# SprinklerControllerRecover.net
KiCad netlist of a schematic drawn in EAGLE
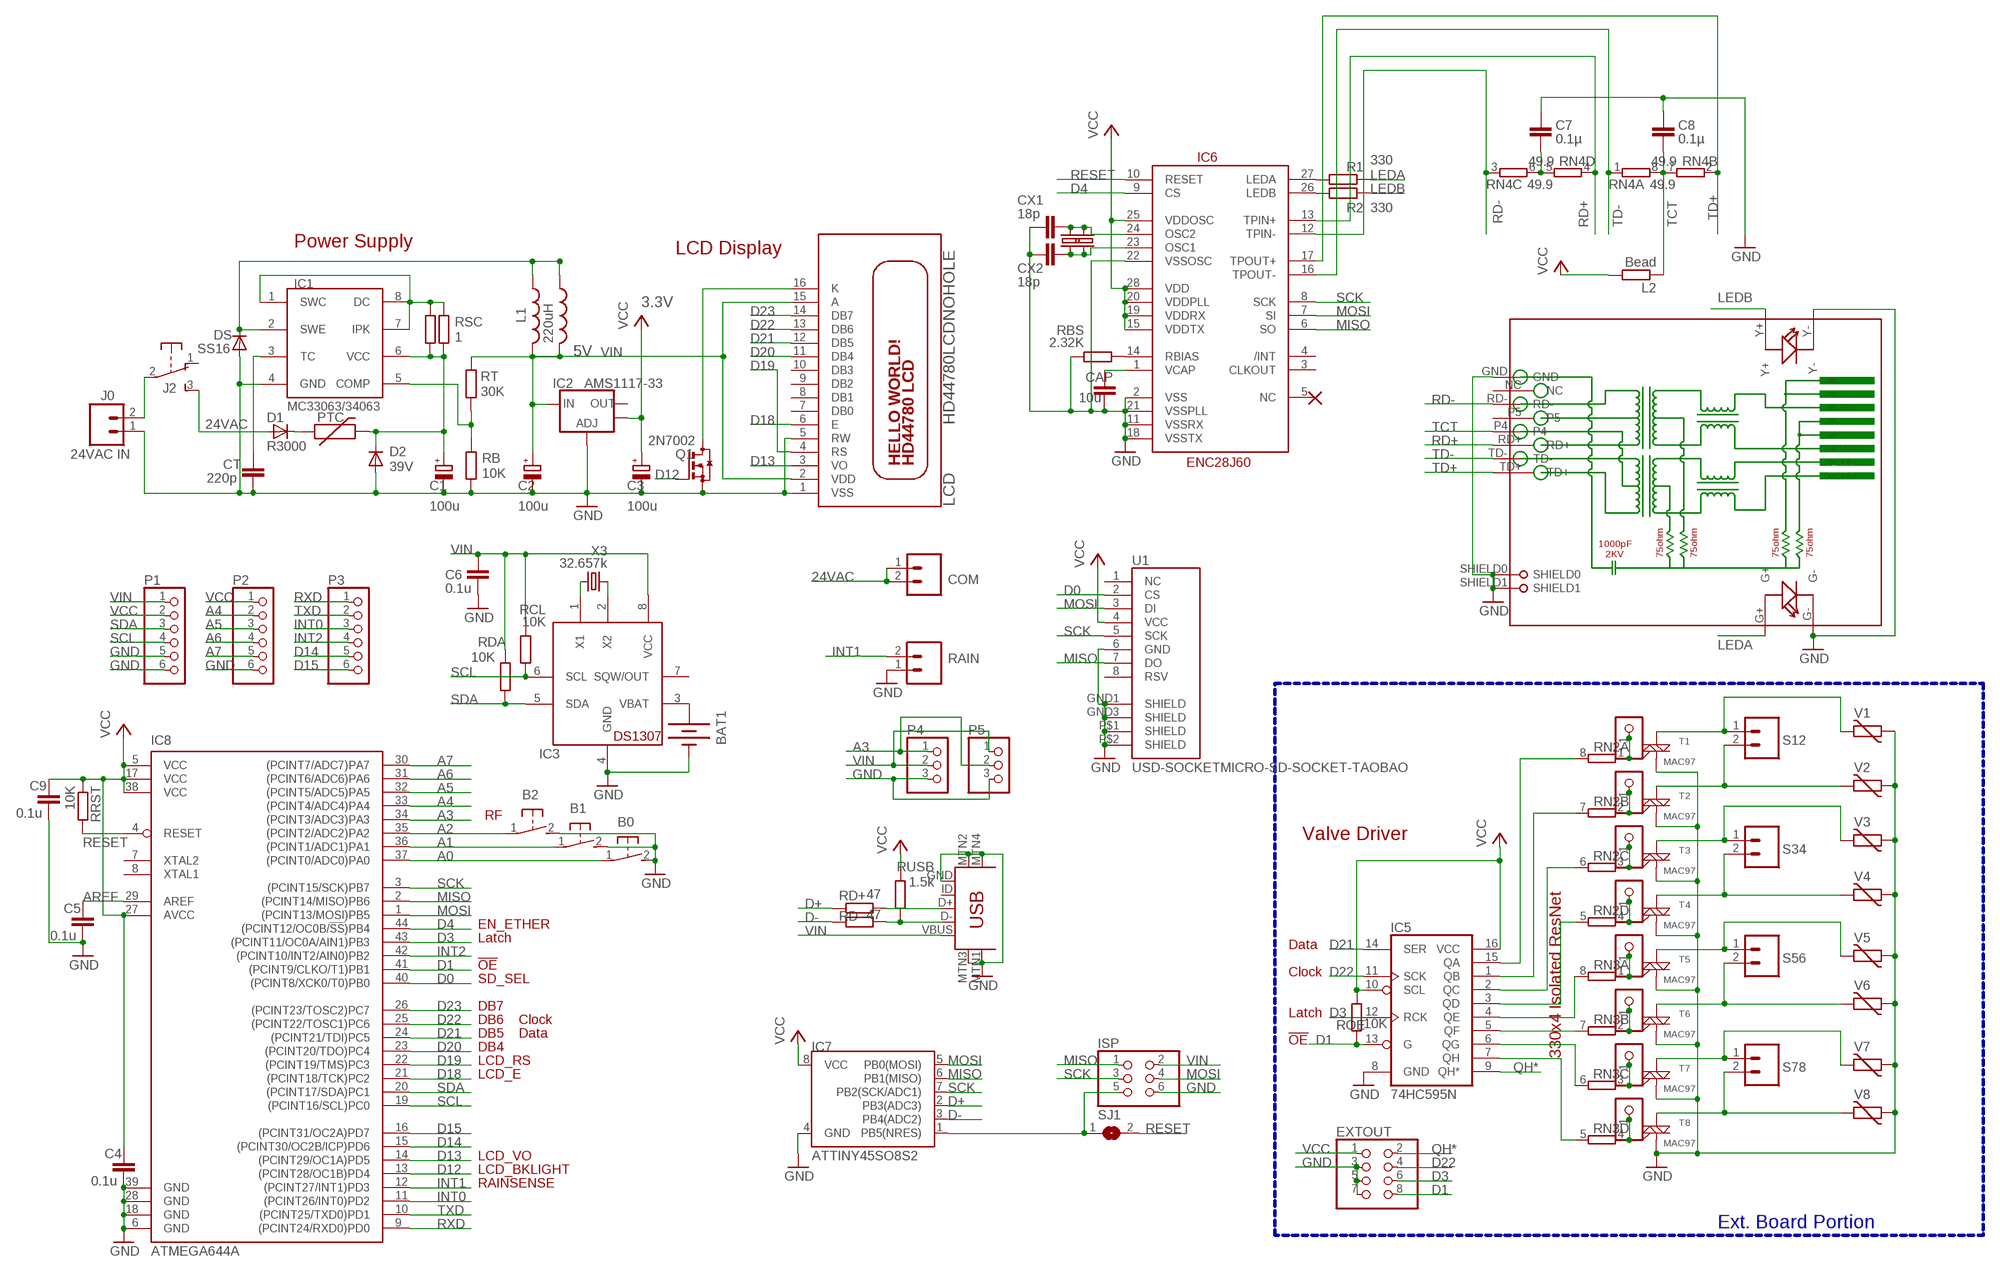
[diagram p0: schematic, sheet 1]

(export (version "E")
  (design (tool "Eeschema 10.0.6"))
  (components
    (comp (ref "B0")
      (value "31-XX")
      (footprint "eagle-import:B3F-31XX")
      (libsource (lib "eagle-import") (part "31-XX"))
    )
    (comp (ref "B1")
      (value "31-XX")
      (footprint "eagle-import:B3F-31XX")
      (libsource (lib "eagle-import") (part "31-XX"))
    )
    (comp (ref "B2")
      (value "31-XX")
      (footprint "eagle-import:B3F-31XX")
      (libsource (lib "eagle-import") (part "31-XX"))
    )
    (comp (ref "BAT1")
      (value "BATTERYBATTERY_12MM_SMT")
      (footprint "eagle-import:BATTCON_12MM_SMT")
      (libsource (lib "eagle-import") (part "BATTERYBATTERY_12MM_SMT"))
    )
    (comp (ref "C1")
      (value "100u")
      (footprint "eagle-import:E3,5-8")
      (libsource (lib "eagle-import") (part "CPOL-EUE3.5-8"))
    )
    (comp (ref "C2")
      (value "100u")
      (footprint "eagle-import:E2,5-5")
      (libsource (lib "eagle-import") (part "CPOL-EUE2.5-5"))
    )
    (comp (ref "C3")
      (value "100u")
      (footprint "eagle-import:E2,5-5")
      (libsource (lib "eagle-import") (part "CPOL-EUE2.5-5"))
    )
    (comp (ref "C4")
      (value "0.1u")
      (footprint "eagle-import:C0805")
      (libsource (lib "eagle-import") (part "C-EUC0805"))
    )
    (comp (ref "C5")
      (value "0.1u")
      (footprint "eagle-import:C0805")
      (libsource (lib "eagle-import") (part "C-EUC0805"))
    )
    (comp (ref "C6")
      (value "0.1u")
      (footprint "eagle-import:C0805")
      (libsource (lib "eagle-import") (part "C-EUC0805"))
    )
    (comp (ref "C7")
      (value "0.1µ")
      (footprint "eagle-import:C0805")
      (libsource (lib "eagle-import") (part "resistor_C-EUC0805"))
    )
    (comp (ref "C8")
      (value "0.1µ")
      (footprint "eagle-import:C0805")
      (libsource (lib "eagle-import") (part "resistor_C-EUC0805"))
    )
    (comp (ref "C9")
      (value "0.1u")
      (footprint "eagle-import:C0805")
      (libsource (lib "eagle-import") (part "C-EUC0805"))
    )
    (comp (ref "CAP")
      (value "10u")
      (footprint "eagle-import:C0805")
      (libsource (lib "eagle-import") (part "resistor_C-EUC0805"))
    )
    (comp (ref "COM")
      (value "M025MM")
      (footprint "eagle-import:SCREWTERMINAL-5MM-2")
      (libsource (lib "eagle-import") (part "M025MM"))
    )
    (comp (ref "CT")
      (value "220p")
      (footprint "eagle-import:C0805")
      (libsource (lib "eagle-import") (part "C-EUC0805"))
    )
    (comp (ref "CX1")
      (value "18p")
      (footprint "eagle-import:C0805")
      (libsource (lib "eagle-import") (part "resistor_C-EUC0805"))
    )
    (comp (ref "CX2")
      (value "18p")
      (footprint "eagle-import:C0805")
      (libsource (lib "eagle-import") (part "resistor_C-EUC0805"))
    )
    (comp (ref "D1")
      (value "R3000")
      (footprint "eagle-import:DO41-7.6")
      (libsource (lib "eagle-import") (part "DIODE-DO41-7.6"))
    )
    (comp (ref "D2")
      (value "39V")
      (footprint "eagle-import:DO41-7.6")
      (libsource (lib "eagle-import") (part "DIODE-DO41-7.6"))
    )
    (comp (ref "DS")
      (value "SS16")
      (footprint "eagle-import:DO214AC")
      (libsource (lib "eagle-import") (part "DIODE-DO214AC"))
    )
    (comp (ref "EXTOUT")
      (value "PINHD-2X4")
      (footprint "eagle-import:2X04")
      (libsource (lib "eagle-import") (part "PINHD-2X4"))
    )
    (comp (ref "IC1")
      (value "MC34063")
      (footprint "eagle-import:SO08")
      (libsource (lib "eagle-import") (part "MC33063/MC34063D"))
    )
    (comp (ref "IC2")
      (value "AMS1117-33")
      (footprint "eagle-import:SOT223")
      (libsource (lib "eagle-import") (part "V_REG_LM1117SOT223"))
    )
    (comp (ref "IC3")
      (value "DS1307")
      (footprint "eagle-import:SO08")
      (libsource (lib "eagle-import") (part "DS1307SOIC"))
    )
    (comp (ref "IC5")
      (value "74HC595N")
      (footprint "eagle-import:SO16")
      (libsource (lib "eagle-import") (part "74595DLS"))
    )
    (comp (ref "IC6")
      (value "ENC28J60")
      (footprint "eagle-import:SOIC28WLONG")
      (libsource (lib "eagle-import") (part "ENC28J60SO28LONG"))
    )
    (comp (ref "IC7")
      (value "ATTINY45SO8S2")
      (footprint "eagle-import:SO8S2")
      (libsource (lib "eagle-import") (part "ATTINY45SO8S2"))
    )
    (comp (ref "IC8")
      (value "ATMEGA644A")
      (footprint "eagle-import:TQFP44")
      (fields (field (name "MPN") "ATMEGA644PV-10AU"))
      (libsource (lib "eagle-import") (part "ATMEGA644A"))
    )
    (comp (ref "ISP")
      (value "PINHD-2X3")
      (footprint "eagle-import:2X03")
      (libsource (lib "eagle-import") (part "PINHD-2X3"))
    )
    (comp (ref "J0")
      (value "24VAC IN")
      (footprint "eagle-import:SCREWTERMINAL-5MM-2")
      (libsource (lib "eagle-import") (part "M025MM"))
    )
    (comp (ref "J2")
      (value "EG1206")
      (footprint "eagle-import:EG1206")
      (libsource (lib "eagle-import") (part "EG1206"))
    )
    (comp (ref "JP2")
      (value "PINHD-1X1CB")
      (footprint "eagle-import:1X01-CLEANBIG")
      (libsource (lib "eagle-import") (part "PINHD-1X1CB"))
    )
    (comp (ref "JP3")
      (value "PINHD-1X1CB")
      (footprint "eagle-import:1X01-CLEANBIG")
      (libsource (lib "eagle-import") (part "PINHD-1X1CB"))
    )
    (comp (ref "JP4")
      (value "PINHD-1X1CB")
      (footprint "eagle-import:1X01-CLEANBIG")
      (libsource (lib "eagle-import") (part "PINHD-1X1CB"))
    )
    (comp (ref "JP5")
      (value "PINHD-1X1CB")
      (footprint "eagle-import:1X01-CLEANBIG")
      (libsource (lib "eagle-import") (part "PINHD-1X1CB"))
    )
    (comp (ref "JP6")
      (value "PINHD-1X1CB")
      (footprint "eagle-import:1X01-CLEANBIG")
      (libsource (lib "eagle-import") (part "PINHD-1X1CB"))
    )
    (comp (ref "JP7")
      (value "PINHD-1X1CB")
      (footprint "eagle-import:1X01-CLEANBIG")
      (libsource (lib "eagle-import") (part "PINHD-1X1CB"))
    )
    (comp (ref "JP8")
      (value "PINHD-1X1CB")
      (footprint "eagle-import:1X01-CLEANBIG")
      (libsource (lib "eagle-import") (part "PINHD-1X1CB"))
    )
    (comp (ref "JP9")
      (value "PINHD-1X1CB")
      (footprint "eagle-import:1X01-CLEANBIG")
      (libsource (lib "eagle-import") (part "PINHD-1X1CB"))
    )
    (comp (ref "L1")
      (value "220uH")
      (footprint "eagle-import:6000-XXXX-RC")
      (libsource (lib "eagle-import") (part "L-US6000-XXX-RC"))
    )
    (comp (ref "L2")
      (value "Bead")
      (footprint "eagle-import:R0805")
      (libsource (lib "eagle-import") (part "R-EU_R0805"))
    )
    (comp (ref "L3")
      (value "220uH")
      (footprint "eagle-import:SRU1038")
      (libsource (lib "eagle-import") (part "INDUCTORSRU1038"))
    )
    (comp (ref "LCD")
      (value "HD44780LCDNOHOLE")
      (footprint "eagle-import:LCD1602A")
      (libsource (lib "eagle-import") (part "HD44780LCDNOHOLE"))
    )
    (comp (ref "P1")
      (value "PINHD-1X6CLEAN")
      (footprint "eagle-import:1X06-CLEAN")
      (libsource (lib "eagle-import") (part "PINHD-1X6CLEAN"))
    )
    (comp (ref "P2")
      (value "PINHD-1X6CLEAN")
      (footprint "eagle-import:1X06-CLEAN")
      (libsource (lib "eagle-import") (part "PINHD-1X6CLEAN"))
    )
    (comp (ref "P3")
      (value "PINHD-1X6CLEAN")
      (footprint "eagle-import:1X06-CLEAN")
      (libsource (lib "eagle-import") (part "PINHD-1X6CLEAN"))
    )
    (comp (ref "P4")
      (value "PINHD-1X3")
      (footprint "eagle-import:1X03")
      (libsource (lib "eagle-import") (part "PINHD-1X3"))
    )
    (comp (ref "P5")
      (value "PINHD-1X3")
      (footprint "eagle-import:1X03")
      (libsource (lib "eagle-import") (part "PINHD-1X3"))
    )
    (comp (ref "PTC")
      (value "PTC")
      (footprint "eagle-import:PTC")
      (libsource (lib "eagle-import") (part "PTCPTH"))
    )
    (comp (ref "Q1")
      (value "2N7002")
      (footprint "eagle-import:SOT23")
      (libsource (lib "eagle-import") (part "BSS123"))
    )
    (comp (ref "R1")
      (value "330")
      (footprint "eagle-import:R0805")
      (libsource (lib "eagle-import") (part "R-EU_R0805"))
    )
    (comp (ref "R2")
      (value "330")
      (footprint "eagle-import:R0805")
      (libsource (lib "eagle-import") (part "R-EU_R0805"))
    )
    (comp (ref "RAIN")
      (value "M025MM")
      (footprint "eagle-import:SCREWTERMINAL-5MM-2")
      (libsource (lib "eagle-import") (part "M025MM"))
    )
    (comp (ref "RB")
      (value "10K")
      (footprint "eagle-import:R0805")
      (libsource (lib "eagle-import") (part "R-EU_R0805"))
    )
    (comp (ref "RBS")
      (value "2.32K")
      (footprint "eagle-import:R0805")
      (libsource (lib "eagle-import") (part "R-EU_R0805"))
    )
    (comp (ref "RCL")
      (value "10K")
      (footprint "eagle-import:R0805")
      (libsource (lib "eagle-import") (part "R-EU_R0805"))
    )
    (comp (ref "RD+")
      (value "47")
      (footprint "eagle-import:R0805")
      (libsource (lib "eagle-import") (part "R-EU_R0805"))
    )
    (comp (ref "RD-")
      (value "47")
      (footprint "eagle-import:R0805")
      (libsource (lib "eagle-import") (part "R-EU_R0805"))
    )
    (comp (ref "RDA")
      (value "10K")
      (footprint "eagle-import:R0805")
      (libsource (lib "eagle-import") (part "R-EU_R0805"))
    )
    (comp (ref "RJ1")
      (value "HR911105A")
      (footprint "eagle-import:HR911105A")
      (libsource (lib "eagle-import") (part "HR911105A"))
    )
    (comp (ref "RN2")
      (value "4R-NEXB38V")
      (footprint "eagle-import:EXB38V")
      (libsource (lib "eagle-import") (part "4R-NEXB38V"))
    )
    (comp (ref "RN3")
      (value "4R-NEXB38V")
      (footprint "eagle-import:EXB38V")
      (libsource (lib "eagle-import") (part "4R-NEXB38V"))
    )
    (comp (ref "RN4")
      (value "49.9")
      (footprint "eagle-import:EXB38V")
      (libsource (lib "eagle-import") (part "4R-NEXB38V"))
    )
    (comp (ref "ROE")
      (value "10K")
      (footprint "eagle-import:R0805")
      (libsource (lib "eagle-import") (part "R-EU_R0805"))
    )
    (comp (ref "RRST")
      (value "10K")
      (footprint "eagle-import:R0805")
      (libsource (lib "eagle-import") (part "R-EU_R0805"))
    )
    (comp (ref "RSC")
      (value "1")
      (footprint "eagle-import:R0805")
      (libsource (lib "eagle-import") (part "R-EU_R0805"))
    )
    (comp (ref "RSC1")
      (value "1.0")
      (footprint "eagle-import:R0805")
      (libsource (lib "eagle-import") (part "R-EU_R0805"))
    )
    (comp (ref "RT")
      (value "30K")
      (footprint "eagle-import:R0805")
      (libsource (lib "eagle-import") (part "R-EU_R0805"))
    )
    (comp (ref "RUSB")
      (value "1.5k")
      (footprint "eagle-import:R0805")
      (libsource (lib "eagle-import") (part "R-EU_R0805"))
    )
    (comp (ref "S12")
      (value "M025MM")
      (footprint "eagle-import:SCREWTERMINAL-5MM-2")
      (libsource (lib "eagle-import") (part "M025MM"))
    )
    (comp (ref "S34")
      (value "M025MM")
      (footprint "eagle-import:SCREWTERMINAL-5MM-2")
      (libsource (lib "eagle-import") (part "M025MM"))
    )
    (comp (ref "S56")
      (value "M025MM")
      (footprint "eagle-import:SCREWTERMINAL-5MM-2")
      (libsource (lib "eagle-import") (part "M025MM"))
    )
    (comp (ref "S78")
      (value "M025MM")
      (footprint "eagle-import:SCREWTERMINAL-5MM-2")
      (libsource (lib "eagle-import") (part "M025MM"))
    )
    (comp (ref "SJ1") (value "SJ") (footprint "eagle-import:SJ") (libsource (lib "eagle-import") (part "SJ")))
    (comp (ref "T1")
      (value "MAC97")
      (footprint "eagle-import:SOT223")
      (libsource (lib "eagle-import") (part "MAC97SOT223"))
    )
    (comp (ref "T2")
      (value "MAC97")
      (footprint "eagle-import:SOT223")
      (libsource (lib "eagle-import") (part "MAC97SOT223"))
    )
    (comp (ref "T3")
      (value "MAC97")
      (footprint "eagle-import:SOT223")
      (libsource (lib "eagle-import") (part "MAC97SOT223"))
    )
    (comp (ref "T4")
      (value "MAC97")
      (footprint "eagle-import:SOT223")
      (libsource (lib "eagle-import") (part "MAC97SOT223"))
    )
    (comp (ref "T5")
      (value "MAC97")
      (footprint "eagle-import:SOT223")
      (libsource (lib "eagle-import") (part "MAC97SOT223"))
    )
    (comp (ref "T6")
      (value "MAC97")
      (footprint "eagle-import:SOT223")
      (libsource (lib "eagle-import") (part "MAC97SOT223"))
    )
    (comp (ref "T7")
      (value "MAC97")
      (footprint "eagle-import:SOT223")
      (libsource (lib "eagle-import") (part "MAC97SOT223"))
    )
    (comp (ref "T8")
      (value "MAC97")
      (footprint "eagle-import:SOT223")
      (libsource (lib "eagle-import") (part "MAC97SOT223"))
    )
    (comp (ref "U$1")
      (value "USB-MINIB-5PIN")
      (footprint "eagle-import:USB-MINIB")
      (libsource (lib "eagle-import") (part "USB-MINIB-5PIN"))
    )
    (comp (ref "U1")
      (value "USD-SOCKETMICRO-SD-SOCKET-TAOBAO")
      (footprint "eagle-import:MICRO-SD-SOCKET-TAOBAO")
      (libsource (lib "eagle-import") (part "USD-SOCKETMICRO-SD-SOCKET-TAOBAO"))
    )
    (comp (ref "V1")
      (value "MOV")
      (footprint "eagle-import:R-5")
      (libsource (lib "eagle-import") (part "VARISTOR-5"))
    )
    (comp (ref "V2")
      (value "MOV")
      (footprint "eagle-import:R-5")
      (libsource (lib "eagle-import") (part "VARISTOR-5"))
    )
    (comp (ref "V3")
      (value "MOV")
      (footprint "eagle-import:R-5")
      (libsource (lib "eagle-import") (part "VARISTOR-5"))
    )
    (comp (ref "V4")
      (value "MOV")
      (footprint "eagle-import:R-5")
      (libsource (lib "eagle-import") (part "VARISTOR-5"))
    )
    (comp (ref "V5")
      (value "MOV")
      (footprint "eagle-import:R-5")
      (libsource (lib "eagle-import") (part "VARISTOR-5"))
    )
    (comp (ref "V6")
      (value "MOV")
      (footprint "eagle-import:R-5")
      (libsource (lib "eagle-import") (part "VARISTOR-5"))
    )
    (comp (ref "V7")
      (value "MOV")
      (footprint "eagle-import:R-5")
      (libsource (lib "eagle-import") (part "VARISTOR-5"))
    )
    (comp (ref "V8")
      (value "MOV")
      (footprint "eagle-import:R-5")
      (libsource (lib "eagle-import") (part "VARISTOR-5"))
    )
    (comp (ref "X2A")
      (value "25MHz")
      (footprint "eagle-import:CRYSTAL-SMD-10.5X4.8-2PIN")
      (libsource (lib "eagle-import") (part "CRYSTAL10.5X4.8"))
    )
    (comp (ref "X2A1")
      (value "25MHz")
      (footprint "eagle-import:HC49US")
      (libsource (lib "eagle-import") (part "CRYSTALHC49US"))
    )
    (comp (ref "X3")
      (value "32.657k")
      (footprint "eagle-import:TC26H")
      (libsource (lib "eagle-import") (part "crystal_CRYSTALTC26H"))
    )
  )
  (nets
    (net (code "1") (name "/24VAC") (class "Default")
      (node (ref "COM") (pin "1") (pinfunction "1_1") (pintype "passive"))
      (node (ref "COM") (pin "2") (pinfunction "2_2") (pintype "passive"))
      (node (ref "D1") (pin "A") (pinfunction "A_A") (pintype "passive"))
      (node (ref "J2") (pin "3") (pinfunction "S_3") (pintype "passive"))
    )
    (net (code "2") (name "/A0") (class "Default")
      (node (ref "B0") (pin "1") (pinfunction "P_1") (pintype "passive"))
      (node (ref "IC8") (pin "37") (pinfunction "(PCINT0/ADC0)PA0_37") (pintype "bidirectional"))
    )
    (net (code "3") (name "/A1") (class "Default")
      (node (ref "B1") (pin "1") (pinfunction "P_1") (pintype "passive"))
      (node (ref "IC8") (pin "36") (pinfunction "(PCINT1/ADC1)PA1_36") (pintype "bidirectional"))
    )
    (net (code "4") (name "/A2") (class "Default")
      (node (ref "B2") (pin "1") (pinfunction "P_1") (pintype "passive"))
      (node (ref "IC8") (pin "35") (pinfunction "(PCINT2/ADC2)PA2_35") (pintype "bidirectional"))
    )
    (net (code "5") (name "/A3") (class "Default")
      (node (ref "IC8") (pin "34") (pinfunction "(PCINT3/ADC3)PA3_34") (pintype "bidirectional"))
      (node (ref "P4") (pin "1") (pinfunction "1_1") (pintype "passive"))
      (node (ref "P5") (pin "2") (pinfunction "2_2") (pintype "passive"))
    )
    (net (code "6") (name "/A4") (class "Default")
      (node (ref "IC8") (pin "33") (pinfunction "(PCINT4/ADC4)PA4_33") (pintype "bidirectional"))
      (node (ref "P2") (pin "2") (pinfunction "2_2") (pintype "passive"))
    )
    (net (code "7") (name "/A5") (class "Default")
      (node (ref "IC8") (pin "32") (pinfunction "(PCINT5/ADC5)PA5_32") (pintype "bidirectional"))
      (node (ref "P2") (pin "3") (pinfunction "3_3") (pintype "passive"))
    )
    (net (code "8") (name "/A6") (class "Default")
      (node (ref "IC8") (pin "31") (pinfunction "(PCINT6/ADC6)PA6_31") (pintype "bidirectional"))
      (node (ref "P2") (pin "4") (pinfunction "4_4") (pintype "passive"))
    )
    (net (code "9") (name "/A7") (class "Default")
      (node (ref "IC8") (pin "30") (pinfunction "(PCINT7/ADC7)PA7_30") (pintype "bidirectional"))
      (node (ref "P2") (pin "5") (pinfunction "5_5") (pintype "passive"))
    )
    (net (code "10") (name "/AREF") (class "Default")
      (node (ref "C5") (pin "1") (pinfunction "1_1") (pintype "passive"))
      (node (ref "IC8") (pin "29") (pinfunction "AREF_29") (pintype "passive"))
    )
    (net (code "11") (name "/D+") (class "Default")
      (node (ref "IC7") (pin "2") (pinfunction "PB3(ADC3)_2") (pintype "bidirectional"))
      (node (ref "RD+") (pin "1") (pinfunction "1_1") (pintype "passive"))
    )
    (net (code "12") (name "/D-") (class "Default")
      (node (ref "IC7") (pin "3") (pinfunction "PB4(ADC2)_3") (pintype "bidirectional"))
      (node (ref "RD-") (pin "1") (pinfunction "1_1") (pintype "passive"))
    )
    (net (code "13") (name "/D0") (class "Default")
      (node (ref "IC8") (pin "40") (pinfunction "(PCINT8/XCK0/T0)PB0_40") (pintype "bidirectional"))
      (node (ref "U1") (pin "2") (pinfunction "CS_2") (pintype "bidirectional"))
    )
    (net (code "14") (name "/D1") (class "Default")
      (node (ref "EXTOUT") (pin "8") (pinfunction "8_8") (pintype "passive"))
      (node (ref "IC5") (pin "13") (pinfunction "G_13") (pintype "input"))
      (node (ref "IC8") (pin "41") (pinfunction "(PCINT9/CLKO/T1)PB1_41") (pintype "bidirectional"))
      (node (ref "ROE") (pin "1") (pinfunction "1_1") (pintype "passive"))
    )
    (net (code "15") (name "/D3") (class "Default")
      (node (ref "EXTOUT") (pin "6") (pinfunction "6_6") (pintype "passive"))
      (node (ref "IC5") (pin "12") (pinfunction "RCK_12") (pintype "input"))
      (node (ref "IC8") (pin "43") (pinfunction "(PCINT11/OC0A/AIN1)PB3_43") (pintype "bidirectional"))
    )
    (net (code "16") (name "/D4") (class "Default")
      (node (ref "IC6") (pin "9") (pinfunction "CS_9") (pintype "bidirectional"))
      (node (ref "IC8") (pin "44") (pinfunction "(PCINT12/OC0B/~{SS})PB4_44") (pintype "bidirectional"))
    )
    (net (code "17") (name "/D12") (class "Default")
      (node (ref "IC8") (pin "13") (pinfunction "(PCINT28/OC1B)PD4_13") (pintype "bidirectional"))
      (node (ref "Q1") (pin "1") (pinfunction "G_1") (pintype "passive"))
    )
    (net (code "18") (name "/D13") (class "Default")
      (node (ref "IC8") (pin "14") (pinfunction "(PCINT29/OC1A)PD5_14") (pintype "bidirectional"))
      (node (ref "LCD") (pin "3") (pinfunction "VO_3") (pintype "input"))
    )
    (net (code "19") (name "/D14") (class "Default")
      (node (ref "IC8") (pin "15") (pinfunction "(PCINT30/OC2B/ICP)PD6_15") (pintype "bidirectional"))
      (node (ref "P3") (pin "5") (pinfunction "5_5") (pintype "passive"))
    )
    (net (code "20") (name "/D15") (class "Default")
      (node (ref "IC8") (pin "16") (pinfunction "(PCINT31/OC2A)PD7_16") (pintype "bidirectional"))
      (node (ref "P3") (pin "6") (pinfunction "6_6") (pintype "passive"))
    )
    (net (code "21") (name "/D18") (class "Default")
      (node (ref "IC8") (pin "21") (pinfunction "(PCINT18/TCK)PC2_21") (pintype "output"))
      (node (ref "LCD") (pin "6") (pinfunction "E_6") (pintype "input"))
    )
    (net (code "22") (name "/D19") (class "Default")
      (node (ref "IC8") (pin "22") (pinfunction "(PCINT19/TMS)PC3_22") (pintype "output"))
      (node (ref "LCD") (pin "4") (pinfunction "RS_4") (pintype "input"))
    )
    (net (code "23") (name "/D20") (class "Default")
      (node (ref "IC8") (pin "23") (pinfunction "(PCINT20/TDO)PC4_23") (pintype "output"))
      (node (ref "LCD") (pin "11") (pinfunction "DB4_11") (pintype "bidirectional"))
    )
    (net (code "24") (name "/D21") (class "Default")
      (node (ref "IC5") (pin "14") (pinfunction "SER_14") (pintype "input"))
      (node (ref "IC8") (pin "24") (pinfunction "(PCINT21/TDI)PC5_24") (pintype "output"))
      (node (ref "LCD") (pin "12") (pinfunction "DB5_12") (pintype "bidirectional"))
    )
    (net (code "25") (name "/D22") (class "Default")
      (node (ref "EXTOUT") (pin "4") (pinfunction "4_4") (pintype "passive"))
      (node (ref "IC5") (pin "11") (pinfunction "SCK_11") (pintype "input"))
      (node (ref "IC8") (pin "25") (pinfunction "(PCINT22/TOSC1)PC6_25") (pintype "output"))
      (node (ref "LCD") (pin "13") (pinfunction "DB6_13") (pintype "bidirectional"))
    )
    (net (code "26") (name "/D23") (class "Default")
      (node (ref "IC8") (pin "26") (pinfunction "(PCINT23/TOSC2)PC7_26") (pintype "output"))
      (node (ref "LCD") (pin "14") (pinfunction "DB7_14") (pintype "bidirectional"))
    )
    (net (code "27") (name "/INT0") (class "Default")
      (node (ref "IC8") (pin "11") (pinfunction "(PCINT26/INT0)PD2_11") (pintype "bidirectional"))
      (node (ref "P3") (pin "3") (pinfunction "3_3") (pintype "passive"))
    )
    (net (code "28") (name "/INT1") (class "Default")
      (node (ref "IC8") (pin "12") (pinfunction "(PCINT27/INT1)PD3_12") (pintype "bidirectional"))
      (node (ref "RAIN") (pin "2") (pinfunction "2_2") (pintype "passive"))
    )
    (net (code "29") (name "/INT2") (class "Default")
      (node (ref "IC8") (pin "42") (pinfunction "(PCINT10/INT2/AIN0)PB2_42") (pintype "bidirectional"))
      (node (ref "P3") (pin "4") (pinfunction "4_4") (pintype "passive"))
    )
    (net (code "30") (name "/LEDA") (class "Default")
      (node (ref "R1") (pin "2") (pinfunction "2_2") (pintype "passive"))
      (node (ref "RJ1") (pin "G+") (pinfunction "G+_G+") (pintype "bidirectional"))
    )
    (net (code "31") (name "/LEDB") (class "Default")
      (node (ref "R2") (pin "2") (pinfunction "2_2") (pintype "passive"))
      (node (ref "RJ1") (pin "Y+") (pinfunction "Y+_Y+") (pintype "bidirectional"))
    )
    (net (code "32") (name "/MISO") (class "Default")
      (node (ref "IC6") (pin "6") (pinfunction "SO_6") (pintype "bidirectional"))
      (node (ref "IC7") (pin "6") (pinfunction "PB1(MISO)_6") (pintype "bidirectional"))
      (node (ref "IC8") (pin "2") (pinfunction "(PCINT14/MISO)PB6_2") (pintype "bidirectional"))
      (node (ref "ISP") (pin "1") (pinfunction "1_1") (pintype "passive"))
      (node (ref "U1") (pin "7") (pinfunction "DO_7") (pintype "bidirectional"))
    )
    (net (code "33") (name "/MOSI") (class "Default")
      (node (ref "IC6") (pin "7") (pinfunction "SI_7") (pintype "bidirectional"))
      (node (ref "IC7") (pin "5") (pinfunction "PB0(MOSI)_5") (pintype "bidirectional"))
      (node (ref "IC8") (pin "1") (pinfunction "(PCINT13/MOSI)PB5_1") (pintype "bidirectional"))
      (node (ref "ISP") (pin "4") (pinfunction "4_4") (pintype "passive"))
      (node (ref "U1") (pin "3") (pinfunction "DI_3") (pintype "bidirectional"))
    )
    (net (code "34") (name "/QH*") (class "Default")
      (node (ref "EXTOUT") (pin "2") (pinfunction "2_2") (pintype "passive"))
      (node (ref "IC5") (pin "9") (pinfunction "QH*_9") (pintype "tri_state"))
    )
    (net (code "35") (name "/RD+") (class "Default")
      (node (ref "IC6") (pin "13") (pinfunction "TPIN+_13") (pintype "bidirectional"))
      (node (ref "RJ1") (pin "RD+") (pinfunction "RD+_RD+") (pintype "bidirectional"))
      (node (ref "RN4") (pin "4") (pinfunction "1_4") (pintype "passive"))
    )
    (net (code "36") (name "/RD-") (class "Default")
      (node (ref "IC6") (pin "12") (pinfunction "TPIN-_12") (pintype "bidirectional"))
      (node (ref "RJ1") (pin "RD-") (pinfunction "RD-_RD-") (pintype "bidirectional"))
      (node (ref "RN4") (pin "3") (pinfunction "1_3") (pintype "passive"))
    )
    (net (code "37") (name "/RESET") (class "Default")
      (node (ref "IC6") (pin "10") (pinfunction "RESET_10") (pintype "bidirectional"))
      (node (ref "IC8") (pin "4") (pinfunction "RESET_4") (pintype "input"))
      (node (ref "RRST") (pin "2") (pinfunction "2_2") (pintype "passive"))
      (node (ref "SJ1") (pin "2") (pinfunction "2_2") (pintype "passive"))
    )
    (net (code "38") (name "/RXD") (class "Default")
      (node (ref "IC8") (pin "9") (pinfunction "(PCINT24/RXD0)PD0_9") (pintype "bidirectional"))
      (node (ref "P3") (pin "1") (pinfunction "1_1") (pintype "passive"))
    )
    (net (code "39") (name "/SCK") (class "Default")
      (node (ref "IC6") (pin "8") (pinfunction "SCK_8") (pintype "bidirectional"))
      (node (ref "IC7") (pin "7") (pinfunction "PB2(SCK/ADC1)_7") (pintype "bidirectional"))
      (node (ref "IC8") (pin "3") (pinfunction "(PCINT15/SCK)PB7_3") (pintype "bidirectional"))
      (node (ref "ISP") (pin "3") (pinfunction "3_3") (pintype "passive"))
      (node (ref "U1") (pin "5") (pinfunction "SCK_5") (pintype "bidirectional"))
    )
    (net (code "40") (name "/SCL") (class "Default")
      (node (ref "IC3") (pin "6") (pinfunction "SCL_6") (pintype "bidirectional"))
      (node (ref "IC8") (pin "19") (pinfunction "(PCINT16/SCL)PC0_19") (pintype "output"))
      (node (ref "P1") (pin "4") (pinfunction "4_4") (pintype "passive"))
      (node (ref "RCL") (pin "2") (pinfunction "2_2") (pintype "passive"))
    )
    (net (code "41") (name "/SDA") (class "Default")
      (node (ref "IC3") (pin "5") (pinfunction "SDA_5") (pintype "bidirectional"))
      (node (ref "IC8") (pin "20") (pinfunction "(PCINT17/SDA)PC1_20") (pintype "output"))
      (node (ref "P1") (pin "3") (pinfunction "3_3") (pintype "passive"))
      (node (ref "RDA") (pin "2") (pinfunction "2_2") (pintype "passive"))
    )
    (net (code "42") (name "/TCT") (class "Default")
      (node (ref "C8") (pin "2") (pinfunction "2_2") (pintype "passive"))
      (node (ref "L2") (pin "1") (pinfunction "1_1") (pintype "passive"))
      (node (ref "RJ1") (pin "P4") (pinfunction "P4_P4") (pintype "bidirectional"))
      (node (ref "RN4") (pin "7") (pinfunction "2_7") (pintype "passive"))
      (node (ref "RN4") (pin "8") (pinfunction "2_8") (pintype "passive"))
    )
    (net (code "43") (name "/TD+") (class "Default")
      (node (ref "IC6") (pin "17") (pinfunction "TPOUT+_17") (pintype "bidirectional"))
      (node (ref "RJ1") (pin "TD+") (pinfunction "TD+_TD+") (pintype "bidirectional"))
      (node (ref "RN4") (pin "2") (pinfunction "1_2") (pintype "passive"))
    )
    (net (code "44") (name "/TD-") (class "Default")
      (node (ref "IC6") (pin "16") (pinfunction "TPOUT-_16") (pintype "bidirectional"))
      (node (ref "RJ1") (pin "TD-") (pinfunction "TD-_TD-") (pintype "bidirectional"))
      (node (ref "RN4") (pin "1") (pinfunction "1_1") (pintype "passive"))
    )
    (net (code "45") (name "/TXD") (class "Default")
      (node (ref "IC8") (pin "10") (pinfunction "(PCINT25/TXD0)PD1_10") (pintype "bidirectional"))
      (node (ref "P3") (pin "2") (pinfunction "2_2") (pintype "passive"))
    )
    (net (code "46") (name "/VIN") (class "Default")
      (node (ref "C2") (pin "+") (pinfunction "+_+") (pintype "passive"))
      (node (ref "C6") (pin "1") (pinfunction "1_1") (pintype "passive"))
      (node (ref "IC2") (pin "3") (pinfunction "IN_3") (pintype "input"))
      (node (ref "IC3") (pin "8") (pinfunction "VCC_8") (pintype "power_in"))
      (node (ref "ISP") (pin "2") (pinfunction "2_2") (pintype "passive"))
      (node (ref "L1") (pin "2") (pinfunction "2_2") (pintype "passive"))
      (node (ref "L3") (pin "2") (pinfunction "2_2") (pintype "passive"))
      (node (ref "LCD") (pin "15") (pinfunction "A_15") (pintype "input"))
      (node (ref "LCD") (pin "2") (pinfunction "VDD_2") (pintype "power_in"))
      (node (ref "P1") (pin "1") (pinfunction "1_1") (pintype "passive"))
      (node (ref "P4") (pin "2") (pinfunction "2_2") (pintype "passive"))
      (node (ref "P5") (pin "1") (pinfunction "1_1") (pintype "passive"))
      (node (ref "RCL") (pin "1") (pinfunction "1_1") (pintype "passive"))
      (node (ref "RDA") (pin "1") (pinfunction "1_1") (pintype "passive"))
      (node (ref "RT") (pin "1") (pinfunction "1_1") (pintype "passive"))
      (node (ref "U$1") (pin "VBUS") (pinfunction "VBUS_VBUS") (pintype "bidirectional"))
    )
    (net (code "47") (name "GND") (class "Default")
      (node (ref "B0") (pin "2") (pinfunction "S_2") (pintype "passive"))
      (node (ref "B1") (pin "2") (pinfunction "S_2") (pintype "passive"))
      (node (ref "B2") (pin "2") (pinfunction "S_2") (pintype "passive"))
      (node (ref "BAT1") (pin "P$1") (pinfunction "-_P$1") (pintype "power_in"))
      (node (ref "C1") (pin "-") (pinfunction "-_-") (pintype "passive"))
      (node (ref "C2") (pin "-") (pinfunction "-_-") (pintype "passive"))
      (node (ref "C3") (pin "-") (pinfunction "-_-") (pintype "passive"))
      (node (ref "C4") (pin "2") (pinfunction "2_2") (pintype "passive"))
      (node (ref "C5") (pin "2") (pinfunction "2_2") (pintype "passive"))
      (node (ref "C6") (pin "2") (pinfunction "2_2") (pintype "passive"))
      (node (ref "C7") (pin "1") (pinfunction "1_1") (pintype "passive"))
      (node (ref "C8") (pin "1") (pinfunction "1_1") (pintype "passive"))
      (node (ref "C9") (pin "2") (pinfunction "2_2") (pintype "passive"))
      (node (ref "CAP") (pin "2") (pinfunction "2_2") (pintype "passive"))
      (node (ref "CT") (pin "2") (pinfunction "2_2") (pintype "passive"))
      (node (ref "CX1") (pin "2") (pinfunction "2_2") (pintype "passive"))
      (node (ref "CX2") (pin "2") (pinfunction "2_2") (pintype "passive"))
      (node (ref "D2") (pin "A") (pinfunction "A_A") (pintype "passive"))
      (node (ref "DS") (pin "A") (pinfunction "A_A") (pintype "passive"))
      (node (ref "EXTOUT") (pin "3") (pinfunction "3_3") (pintype "passive"))
      (node (ref "EXTOUT") (pin "5") (pinfunction "5_5") (pintype "passive"))
      (node (ref "EXTOUT") (pin "7") (pinfunction "7_7") (pintype "passive"))
      (node (ref "IC1") (pin "4") (pinfunction "GND_4") (pintype "power_in"))
      (node (ref "IC2") (pin "1") (pinfunction "ADJ_1") (pintype "input"))
      (node (ref "IC3") (pin "4") (pinfunction "GND_4") (pintype "power_in"))
      (node (ref "IC5") (pin "8") (pinfunction "GND_8") (pintype "power_in"))
      (node (ref "IC6") (pin "11") (pinfunction "VSSRX_11") (pintype "bidirectional"))
      (node (ref "IC6") (pin "18") (pinfunction "VSSTX_18") (pintype "bidirectional"))
      (node (ref "IC6") (pin "2") (pinfunction "VSS_2") (pintype "bidirectional"))
      (node (ref "IC6") (pin "21") (pinfunction "VSSPLL_21") (pintype "bidirectional"))
      (node (ref "IC6") (pin "22") (pinfunction "VSSOSC_22") (pintype "bidirectional"))
      (node (ref "IC7") (pin "4") (pinfunction "GND_4") (pintype "bidirectional"))
      (node (ref "IC8") (pin "18") (pinfunction "GND_18") (pintype "power_in"))
      (node (ref "IC8") (pin "28") (pinfunction "GND_28") (pintype "power_in"))
      (node (ref "IC8") (pin "39") (pinfunction "GND_39") (pintype "power_in"))
      (node (ref "IC8") (pin "6") (pinfunction "GND_6") (pintype "power_in"))
      (node (ref "ISP") (pin "6") (pinfunction "6_6") (pintype "passive"))
      (node (ref "J0") (pin "1") (pinfunction "1_1") (pintype "passive"))
      (node (ref "LCD") (pin "1") (pinfunction "VSS_1") (pintype "power_in"))
      (node (ref "LCD") (pin "5") (pinfunction "RW_5") (pintype "input"))
      (node (ref "P1") (pin "5") (pinfunction "5_5") (pintype "passive"))
      (node (ref "P1") (pin "6") (pinfunction "6_6") (pintype "passive"))
      (node (ref "P2") (pin "6") (pinfunction "6_6") (pintype "passive"))
      (node (ref "P4") (pin "3") (pinfunction "3_3") (pintype "passive"))
      (node (ref "P5") (pin "3") (pinfunction "3_3") (pintype "passive"))
      (node (ref "Q1") (pin "2") (pinfunction "S_2") (pintype "passive"))
      (node (ref "RAIN") (pin "1") (pinfunction "1_1") (pintype "passive"))
      (node (ref "RB") (pin "2") (pinfunction "2_2") (pintype "passive"))
      (node (ref "RBS") (pin "1") (pinfunction "1_1") (pintype "passive"))
      (node (ref "RJ1") (pin "G-") (pinfunction "G-_G-") (pintype "bidirectional"))
      (node (ref "RJ1") (pin "GND") (pinfunction "GND_GND") (pintype "bidirectional"))
      (node (ref "RJ1") (pin "SHIELD0") (pinfunction "SHIELD0_SHIELD0") (pintype "bidirectional"))
      (node (ref "RJ1") (pin "SHIELD1") (pinfunction "SHIELD1_SHIELD1") (pintype "bidirectional"))
      (node (ref "RJ1") (pin "Y-") (pinfunction "Y-_Y-") (pintype "bidirectional"))
      (node (ref "T1") (pin "1") (pinfunction "M1_1") (pintype "bidirectional"))
      (node (ref "T2") (pin "1") (pinfunction "M1_1") (pintype "bidirectional"))
      (node (ref "T3") (pin "1") (pinfunction "M1_1") (pintype "bidirectional"))
      (node (ref "T4") (pin "1") (pinfunction "M1_1") (pintype "bidirectional"))
      (node (ref "T5") (pin "1") (pinfunction "M1_1") (pintype "bidirectional"))
      (node (ref "T6") (pin "1") (pinfunction "M1_1") (pintype "bidirectional"))
      (node (ref "T7") (pin "1") (pinfunction "M1_1") (pintype "bidirectional"))
      (node (ref "T8") (pin "1") (pinfunction "M1_1") (pintype "bidirectional"))
      (node (ref "U$1") (pin "GND") (pinfunction "GND_GND") (pintype "bidirectional"))
      (node (ref "U$1") (pin "MTN1") (pinfunction "MTN2_MTN1") (pintype "bidirectional"))
      (node (ref "U$1") (pin "MTN2") (pinfunction "MTN3_MTN2") (pintype "bidirectional"))
      (node (ref "U$1") (pin "MTN3") (pinfunction "MTN1_MTN3") (pintype "bidirectional"))
      (node (ref "U$1") (pin "MTN4") (pinfunction "MTN4_MTN4") (pintype "bidirectional"))
      (node (ref "U1") (pin "6") (pinfunction "GND_6") (pintype "bidirectional"))
      (node (ref "U1") (pin "GND1") (pinfunction "SHIELD_GND1") (pintype "bidirectional"))
      (node (ref "U1") (pin "GND3") (pinfunction "SHIELD_GND3") (pintype "bidirectional"))
      (node (ref "U1") (pin "P$1") (pinfunction "SHIELD_P$1") (pintype "bidirectional"))
      (node (ref "U1") (pin "P$2") (pinfunction "SHIELD_P$2") (pintype "bidirectional"))
      (node (ref "V1") (pin "1") (pinfunction "1_1") (pintype "passive"))
      (node (ref "V2") (pin "1") (pinfunction "1_1") (pintype "passive"))
      (node (ref "V3") (pin "1") (pinfunction "1_1") (pintype "passive"))
      (node (ref "V4") (pin "1") (pinfunction "1_1") (pintype "passive"))
      (node (ref "V5") (pin "1") (pinfunction "1_1") (pintype "passive"))
      (node (ref "V6") (pin "1") (pinfunction "1_1") (pintype "passive"))
      (node (ref "V7") (pin "1") (pinfunction "1_1") (pintype "passive"))
      (node (ref "V8") (pin "1") (pinfunction "1_1") (pintype "passive"))
    )
    (net (code "48") (name "Net-(BAT1-+)") (class "Default")
      (node (ref "BAT1") (pin "P$2") (pinfunction "+_P$2") (pintype "power_in"))
      (node (ref "IC3") (pin "3") (pinfunction "VBAT_3") (pintype "power_in"))
    )
    (net (code "49") (name "Net-(IC1-COMP)") (class "Default")
      (node (ref "IC1") (pin "5") (pinfunction "COMP_5") (pintype "input"))
      (node (ref "RB") (pin "1") (pinfunction "1_1") (pintype "passive"))
      (node (ref "RT") (pin "2") (pinfunction "2_2") (pintype "passive"))
    )
    (net (code "50") (name "Net-(IC1-DC)") (class "Default")
      (node (ref "IC1") (pin "1") (pinfunction "SWC_1") (pintype "input"))
      (node (ref "IC1") (pin "7") (pinfunction "IPK_7") (pintype "bidirectional"))
      (node (ref "IC1") (pin "8") (pinfunction "DC_8") (pintype "input"))
      (node (ref "RSC") (pin "1") (pinfunction "1_1") (pintype "passive"))
      (node (ref "RSC1") (pin "1") (pinfunction "1_1") (pintype "passive"))
    )
    (net (code "51") (name "Net-(IC1-SWE)") (class "Default")
      (node (ref "DS") (pin "C") (pinfunction "C_C") (pintype "passive"))
      (node (ref "IC1") (pin "2") (pinfunction "SWE_2") (pintype "input"))
      (node (ref "L1") (pin "1") (pinfunction "1_1") (pintype "passive"))
      (node (ref "L3") (pin "1") (pinfunction "1_1") (pintype "passive"))
    )
    (net (code "52") (name "Net-(IC1-TC)") (class "Default")
      (node (ref "CT") (pin "1") (pinfunction "1_1") (pintype "passive"))
      (node (ref "IC1") (pin "3") (pinfunction "TC_3") (pintype "input"))
    )
    (net (code "53") (name "Net-(IC1-VCC)") (class "Default")
      (node (ref "C1") (pin "+") (pinfunction "+_+") (pintype "passive"))
      (node (ref "D2") (pin "C") (pinfunction "C_C") (pintype "passive"))
      (node (ref "IC1") (pin "6") (pinfunction "VCC_6") (pintype "power_in"))
      (node (ref "PTC") (pin "P$2") (pinfunction "2_P$2") (pintype "bidirectional"))
      (node (ref "RSC") (pin "2") (pinfunction "2_2") (pintype "passive"))
      (node (ref "RSC1") (pin "2") (pinfunction "2_2") (pintype "passive"))
    )
    (net (code "54") (name "Net-(IC3-X1)") (class "Default")
      (node (ref "IC3") (pin "1") (pinfunction "X1_1") (pintype "passive"))
      (node (ref "X3") (pin "1") (pinfunction "1_1") (pintype "passive"))
    )
    (net (code "55") (name "Net-(IC3-X2)") (class "Default")
      (node (ref "IC3") (pin "2") (pinfunction "X2_2") (pintype "passive"))
      (node (ref "X3") (pin "2") (pinfunction "2_2") (pintype "passive"))
    )
    (net (code "56") (name "Net-(IC5-QA)") (class "Default")
      (node (ref "IC5") (pin "15") (pinfunction "QA_15") (pintype "tri_state"))
      (node (ref "RN2") (pin "8") (pinfunction "2_8") (pintype "passive"))
    )
    (net (code "57") (name "Net-(IC5-QB)") (class "Default")
      (node (ref "IC5") (pin "1") (pinfunction "QB_1") (pintype "tri_state"))
      (node (ref "RN2") (pin "7") (pinfunction "2_7") (pintype "passive"))
    )
    (net (code "58") (name "Net-(IC5-QC)") (class "Default")
      (node (ref "IC5") (pin "2") (pinfunction "QC_2") (pintype "tri_state"))
      (node (ref "RN2") (pin "6") (pinfunction "2_6") (pintype "passive"))
    )
    (net (code "59") (name "Net-(IC5-QD)") (class "Default")
      (node (ref "IC5") (pin "3") (pinfunction "QD_3") (pintype "tri_state"))
      (node (ref "RN2") (pin "5") (pinfunction "2_5") (pintype "passive"))
    )
    (net (code "60") (name "Net-(IC5-QE)") (class "Default")
      (node (ref "IC5") (pin "4") (pinfunction "QE_4") (pintype "tri_state"))
      (node (ref "RN3") (pin "8") (pinfunction "2_8") (pintype "passive"))
    )
    (net (code "61") (name "Net-(IC5-QF)") (class "Default")
      (node (ref "IC5") (pin "5") (pinfunction "QF_5") (pintype "tri_state"))
      (node (ref "RN3") (pin "7") (pinfunction "2_7") (pintype "passive"))
    )
    (net (code "62") (name "Net-(IC5-QG)") (class "Default")
      (node (ref "IC5") (pin "6") (pinfunction "QG_6") (pintype "tri_state"))
      (node (ref "RN3") (pin "6") (pinfunction "2_6") (pintype "passive"))
    )
    (net (code "63") (name "Net-(IC5-QH)") (class "Default")
      (node (ref "IC5") (pin "7") (pinfunction "QH_7") (pintype "tri_state"))
      (node (ref "RN3") (pin "5") (pinfunction "2_5") (pintype "passive"))
    )
    (net (code "64") (name "Net-(IC6-LEDA)") (class "Default")
      (node (ref "IC6") (pin "27") (pinfunction "LEDA_27") (pintype "bidirectional"))
      (node (ref "R1") (pin "1") (pinfunction "1_1") (pintype "passive"))
    )
    (net (code "65") (name "Net-(IC6-LEDB)") (class "Default")
      (node (ref "IC6") (pin "26") (pinfunction "LEDB_26") (pintype "bidirectional"))
      (node (ref "R2") (pin "1") (pinfunction "1_1") (pintype "passive"))
    )
    (net (code "66") (name "Net-(IC6-OSC1)") (class "Default")
      (node (ref "CX2") (pin "1") (pinfunction "1_1") (pintype "passive"))
      (node (ref "IC6") (pin "23") (pinfunction "OSC1_23") (pintype "bidirectional"))
      (node (ref "X2A") (pin "P$1") (pinfunction "1_P$1") (pintype "passive"))
      (node (ref "X2A1") (pin "1") (pinfunction "1_1") (pintype "passive"))
    )
    (net (code "67") (name "Net-(IC6-OSC2)") (class "Default")
      (node (ref "CX1") (pin "1") (pinfunction "1_1") (pintype "passive"))
      (node (ref "IC6") (pin "24") (pinfunction "OSC2_24") (pintype "bidirectional"))
      (node (ref "X2A") (pin "P$2") (pinfunction "2_P$2") (pintype "passive"))
      (node (ref "X2A1") (pin "2") (pinfunction "2_2") (pintype "passive"))
    )
    (net (code "68") (name "Net-(IC6-RBIAS)") (class "Default")
      (node (ref "IC6") (pin "14") (pinfunction "RBIAS_14") (pintype "bidirectional"))
      (node (ref "RBS") (pin "2") (pinfunction "2_2") (pintype "passive"))
    )
    (net (code "69") (name "Net-(IC6-VCAP)") (class "Default")
      (node (ref "CAP") (pin "1") (pinfunction "1_1") (pintype "passive"))
      (node (ref "IC6") (pin "1") (pinfunction "VCAP_1") (pintype "bidirectional"))
    )
    (net (code "70") (name "Net-(IC7-PB5(NRES))") (class "Default")
      (node (ref "IC7") (pin "1") (pinfunction "PB5(NRES)_1") (pintype "bidirectional"))
      (node (ref "ISP") (pin "5") (pinfunction "5_5") (pintype "passive"))
      (node (ref "SJ1") (pin "1") (pinfunction "1_1") (pintype "passive"))
    )
    (net (code "71") (name "Net-(J2-P)") (class "Default")
      (node (ref "J0") (pin "2") (pinfunction "2_2") (pintype "passive"))
      (node (ref "J2") (pin "2") (pinfunction "P_2") (pintype "passive"))
    )
    (net (code "72") (name "Net-(LCD-K)") (class "Default")
      (node (ref "LCD") (pin "16") (pinfunction "K_16") (pintype "input"))
      (node (ref "Q1") (pin "3") (pinfunction "D_3") (pintype "passive"))
    )
    (net (code "73") (name "Net-(PTC-1)") (class "Default")
      (node (ref "D1") (pin "C") (pinfunction "C_C") (pintype "passive"))
      (node (ref "PTC") (pin "P$1") (pinfunction "1_P$1") (pintype "bidirectional"))
    )
    (net (code "74") (name "Net-(RD+-Pad2)") (class "Default")
      (node (ref "RD+") (pin "2") (pinfunction "2_2") (pintype "passive"))
      (node (ref "U$1") (pin "D+") (pinfunction "D+_D+") (pintype "bidirectional"))
    )
    (net (code "75") (name "Net-(RD--Pad2)") (class "Default")
      (node (ref "RD-") (pin "2") (pinfunction "2_2") (pintype "passive"))
      (node (ref "RUSB") (pin "1") (pinfunction "1_1") (pintype "passive"))
      (node (ref "U$1") (pin "D-") (pinfunction "D-_D-") (pintype "bidirectional"))
    )
    (net (code "76") (name "Net-(RN2B-1)") (class "Default")
      (node (ref "JP3") (pin "1") (pinfunction "1_1") (pintype "passive"))
      (node (ref "RN2") (pin "2") (pinfunction "1_2") (pintype "passive"))
      (node (ref "T2") (pin "3") (pinfunction "G_3") (pintype "bidirectional"))
    )
    (net (code "77") (name "Net-(RN2C-1)") (class "Default")
      (node (ref "JP4") (pin "1") (pinfunction "1_1") (pintype "passive"))
      (node (ref "RN2") (pin "3") (pinfunction "1_3") (pintype "passive"))
      (node (ref "T3") (pin "3") (pinfunction "G_3") (pintype "bidirectional"))
    )
    (net (code "78") (name "Net-(RN2D-1)") (class "Default")
      (node (ref "JP5") (pin "1") (pinfunction "1_1") (pintype "passive"))
      (node (ref "RN2") (pin "4") (pinfunction "1_4") (pintype "passive"))
      (node (ref "T4") (pin "3") (pinfunction "G_3") (pintype "bidirectional"))
    )
    (net (code "79") (name "Net-(RN3B-1)") (class "Default")
      (node (ref "JP7") (pin "1") (pinfunction "1_1") (pintype "passive"))
      (node (ref "RN3") (pin "2") (pinfunction "1_2") (pintype "passive"))
      (node (ref "T6") (pin "3") (pinfunction "G_3") (pintype "bidirectional"))
    )
    (net (code "80") (name "Net-(RN3C-1)") (class "Default")
      (node (ref "JP8") (pin "1") (pinfunction "1_1") (pintype "passive"))
      (node (ref "RN3") (pin "3") (pinfunction "1_3") (pintype "passive"))
      (node (ref "T7") (pin "3") (pinfunction "G_3") (pintype "bidirectional"))
    )
    (net (code "81") (name "Net-(RN3D-1)") (class "Default")
      (node (ref "JP9") (pin "1") (pinfunction "1_1") (pintype "passive"))
      (node (ref "RN3") (pin "4") (pinfunction "1_4") (pintype "passive"))
      (node (ref "T8") (pin "3") (pinfunction "G_3") (pintype "bidirectional"))
    )
    (net (code "82") (name "Net-(RN4C-2)") (class "Default")
      (node (ref "C7") (pin "2") (pinfunction "2_2") (pintype "passive"))
      (node (ref "RN4") (pin "5") (pinfunction "2_5") (pintype "passive"))
      (node (ref "RN4") (pin "6") (pinfunction "2_6") (pintype "passive"))
    )
    (net (code "83") (name "Net-(T1-G)") (class "Default")
      (node (ref "JP2") (pin "1") (pinfunction "1_1") (pintype "passive"))
      (node (ref "RN2") (pin "1") (pinfunction "1_1") (pintype "passive"))
      (node (ref "T1") (pin "3") (pinfunction "G_3") (pintype "bidirectional"))
    )
    (net (code "84") (name "Net-(T1-M2)") (class "Default")
      (node (ref "S12") (pin "1") (pinfunction "1_1") (pintype "passive"))
      (node (ref "T1") (pin "4") (pinfunction "M2_4") (pintype "bidirectional"))
      (node (ref "V1") (pin "2") (pinfunction "2_2") (pintype "passive"))
    )
    (net (code "85") (name "Net-(T2-M2)") (class "Default")
      (node (ref "S12") (pin "2") (pinfunction "2_2") (pintype "passive"))
      (node (ref "T2") (pin "4") (pinfunction "M2_4") (pintype "bidirectional"))
      (node (ref "V2") (pin "2") (pinfunction "2_2") (pintype "passive"))
    )
    (net (code "86") (name "Net-(T3-M2)") (class "Default")
      (node (ref "S34") (pin "1") (pinfunction "1_1") (pintype "passive"))
      (node (ref "T3") (pin "4") (pinfunction "M2_4") (pintype "bidirectional"))
      (node (ref "V3") (pin "2") (pinfunction "2_2") (pintype "passive"))
    )
    (net (code "87") (name "Net-(T4-M2)") (class "Default")
      (node (ref "S34") (pin "2") (pinfunction "2_2") (pintype "passive"))
      (node (ref "T4") (pin "4") (pinfunction "M2_4") (pintype "bidirectional"))
      (node (ref "V4") (pin "2") (pinfunction "2_2") (pintype "passive"))
    )
    (net (code "88") (name "Net-(T5-G)") (class "Default")
      (node (ref "JP6") (pin "1") (pinfunction "1_1") (pintype "passive"))
      (node (ref "RN3") (pin "1") (pinfunction "1_1") (pintype "passive"))
      (node (ref "T5") (pin "3") (pinfunction "G_3") (pintype "bidirectional"))
    )
    (net (code "89") (name "Net-(T5-M2)") (class "Default")
      (node (ref "S56") (pin "1") (pinfunction "1_1") (pintype "passive"))
      (node (ref "T5") (pin "4") (pinfunction "M2_4") (pintype "bidirectional"))
      (node (ref "V5") (pin "2") (pinfunction "2_2") (pintype "passive"))
    )
    (net (code "90") (name "Net-(T6-M2)") (class "Default")
      (node (ref "S56") (pin "2") (pinfunction "2_2") (pintype "passive"))
      (node (ref "T6") (pin "4") (pinfunction "M2_4") (pintype "bidirectional"))
      (node (ref "V6") (pin "2") (pinfunction "2_2") (pintype "passive"))
    )
    (net (code "91") (name "Net-(T7-M2)") (class "Default")
      (node (ref "S78") (pin "1") (pinfunction "1_1") (pintype "passive"))
      (node (ref "T7") (pin "4") (pinfunction "M2_4") (pintype "bidirectional"))
      (node (ref "V7") (pin "2") (pinfunction "2_2") (pintype "passive"))
    )
    (net (code "92") (name "Net-(T8-M2)") (class "Default")
      (node (ref "S78") (pin "2") (pinfunction "2_2") (pintype "passive"))
      (node (ref "T8") (pin "4") (pinfunction "M2_4") (pintype "bidirectional"))
      (node (ref "V8") (pin "2") (pinfunction "2_2") (pintype "passive"))
    )
    (net (code "93") (name "VCC") (class "Default")
      (node (ref "C3") (pin "+") (pinfunction "+_+") (pintype "passive"))
      (node (ref "C4") (pin "1") (pinfunction "1_1") (pintype "passive"))
      (node (ref "C9") (pin "1") (pinfunction "1_1") (pintype "passive"))
      (node (ref "EXTOUT") (pin "1") (pinfunction "1_1") (pintype "passive"))
      (node (ref "IC2") (pin "4") (pinfunction "OUT_4") (pintype "bidirectional"))
      (node (ref "IC5") (pin "10") (pinfunction "SCL_10") (pintype "input"))
      (node (ref "IC5") (pin "16") (pinfunction "VCC_16") (pintype "power_in"))
      (node (ref "IC6") (pin "15") (pinfunction "VDDTX_15") (pintype "bidirectional"))
      (node (ref "IC6") (pin "19") (pinfunction "VDDRX_19") (pintype "bidirectional"))
      (node (ref "IC6") (pin "20") (pinfunction "VDDPLL_20") (pintype "bidirectional"))
      (node (ref "IC6") (pin "25") (pinfunction "VDDOSC_25") (pintype "bidirectional"))
      (node (ref "IC6") (pin "28") (pinfunction "VDD_28") (pintype "bidirectional"))
      (node (ref "IC7") (pin "8") (pinfunction "VCC_8") (pintype "bidirectional"))
      (node (ref "IC8") (pin "17") (pinfunction "VCC_17") (pintype "power_in"))
      (node (ref "IC8") (pin "27") (pinfunction "AVCC_27") (pintype "power_in"))
      (node (ref "IC8") (pin "38") (pinfunction "VCC_38") (pintype "power_in"))
      (node (ref "IC8") (pin "5") (pinfunction "VCC_5") (pintype "power_in"))
      (node (ref "L2") (pin "2") (pinfunction "2_2") (pintype "passive"))
      (node (ref "P1") (pin "2") (pinfunction "2_2") (pintype "passive"))
      (node (ref "P2") (pin "1") (pinfunction "1_1") (pintype "passive"))
      (node (ref "ROE") (pin "2") (pinfunction "2_2") (pintype "passive"))
      (node (ref "RRST") (pin "1") (pinfunction "1_1") (pintype "passive"))
      (node (ref "RUSB") (pin "2") (pinfunction "2_2") (pintype "passive"))
      (node (ref "U1") (pin "4") (pinfunction "VCC_4") (pintype "bidirectional"))
    )
    (net (code "94") (name "unconnected-(IC2-OUT-Pad2)") (class "Default")
      (node (ref "IC2") (pin "2") (pinfunction "OUT_2") (pintype "bidirectional"))
    )
    (net (code "95") (name "unconnected-(IC3-SQW{slash}OUT-Pad7)") (class "Default")
      (node (ref "IC3") (pin "7") (pinfunction "SQW/OUT_7") (pintype "bidirectional"))
    )
    (net (code "96") (name "unconnected-(IC6-CLKOUT-Pad3)") (class "Default")
      (node (ref "IC6") (pin "3") (pinfunction "CLKOUT_3") (pintype "bidirectional"))
    )
    (net (code "97") (name "unconnected-(IC6-NC-Pad5)") (class "Default")
      (node (ref "IC6") (pin "5") (pinfunction "NC_5") (pintype "bidirectional"))
    )
    (net (code "98") (name "unconnected-(IC6-{slash}INT-Pad4)") (class "Default")
      (node (ref "IC6") (pin "4") (pinfunction "/INT_4") (pintype "bidirectional"))
    )
    (net (code "99") (name "unconnected-(IC8-XTAL1-Pad8)") (class "Default")
      (node (ref "IC8") (pin "8") (pinfunction "XTAL1_8") (pintype "bidirectional"))
    )
    (net (code "100") (name "unconnected-(IC8-XTAL2-Pad7)") (class "Default")
      (node (ref "IC8") (pin "7") (pinfunction "XTAL2_7") (pintype "bidirectional"))
    )
    (net (code "101") (name "unconnected-(J2-O-Pad1)") (class "Default")
      (node (ref "J2") (pin "1") (pinfunction "O_1") (pintype "passive"))
    )
    (net (code "102") (name "unconnected-(LCD-DB0-Pad7)") (class "Default")
      (node (ref "LCD") (pin "7") (pinfunction "DB0_7") (pintype "bidirectional"))
    )
    (net (code "103") (name "unconnected-(LCD-DB1-Pad8)") (class "Default")
      (node (ref "LCD") (pin "8") (pinfunction "DB1_8") (pintype "bidirectional"))
    )
    (net (code "104") (name "unconnected-(LCD-DB2-Pad9)") (class "Default")
      (node (ref "LCD") (pin "9") (pinfunction "DB2_9") (pintype "bidirectional"))
    )
    (net (code "105") (name "unconnected-(LCD-DB3-Pad10)") (class "Default")
      (node (ref "LCD") (pin "10") (pinfunction "DB3_10") (pintype "bidirectional"))
    )
    (net (code "106") (name "unconnected-(RJ1-PadNC)") (class "Default")
      (node (ref "RJ1") (pin "NC") (pinfunction "NC_NC") (pintype "bidirectional"))
    )
    (net (code "107") (name "unconnected-(RJ1-PadP5)") (class "Default")
      (node (ref "RJ1") (pin "P5") (pinfunction "P5_P5") (pintype "bidirectional"))
    )
    (net (code "108") (name "unconnected-(U$1-PadID)") (class "Default")
      (node (ref "U$1") (pin "ID") (pinfunction "ID_ID") (pintype "bidirectional"))
    )
    (net (code "109") (name "unconnected-(U1-NC-Pad1)") (class "Default")
      (node (ref "U1") (pin "1") (pinfunction "NC_1") (pintype "bidirectional"))
    )
    (net (code "110") (name "unconnected-(U1-RSV-Pad8)") (class "Default")
      (node (ref "U1") (pin "8") (pinfunction "RSV_8") (pintype "bidirectional"))
    )
  )
)
